# 07_Communication.net
KiCad netlist of a schematic drawn in Altium Designer
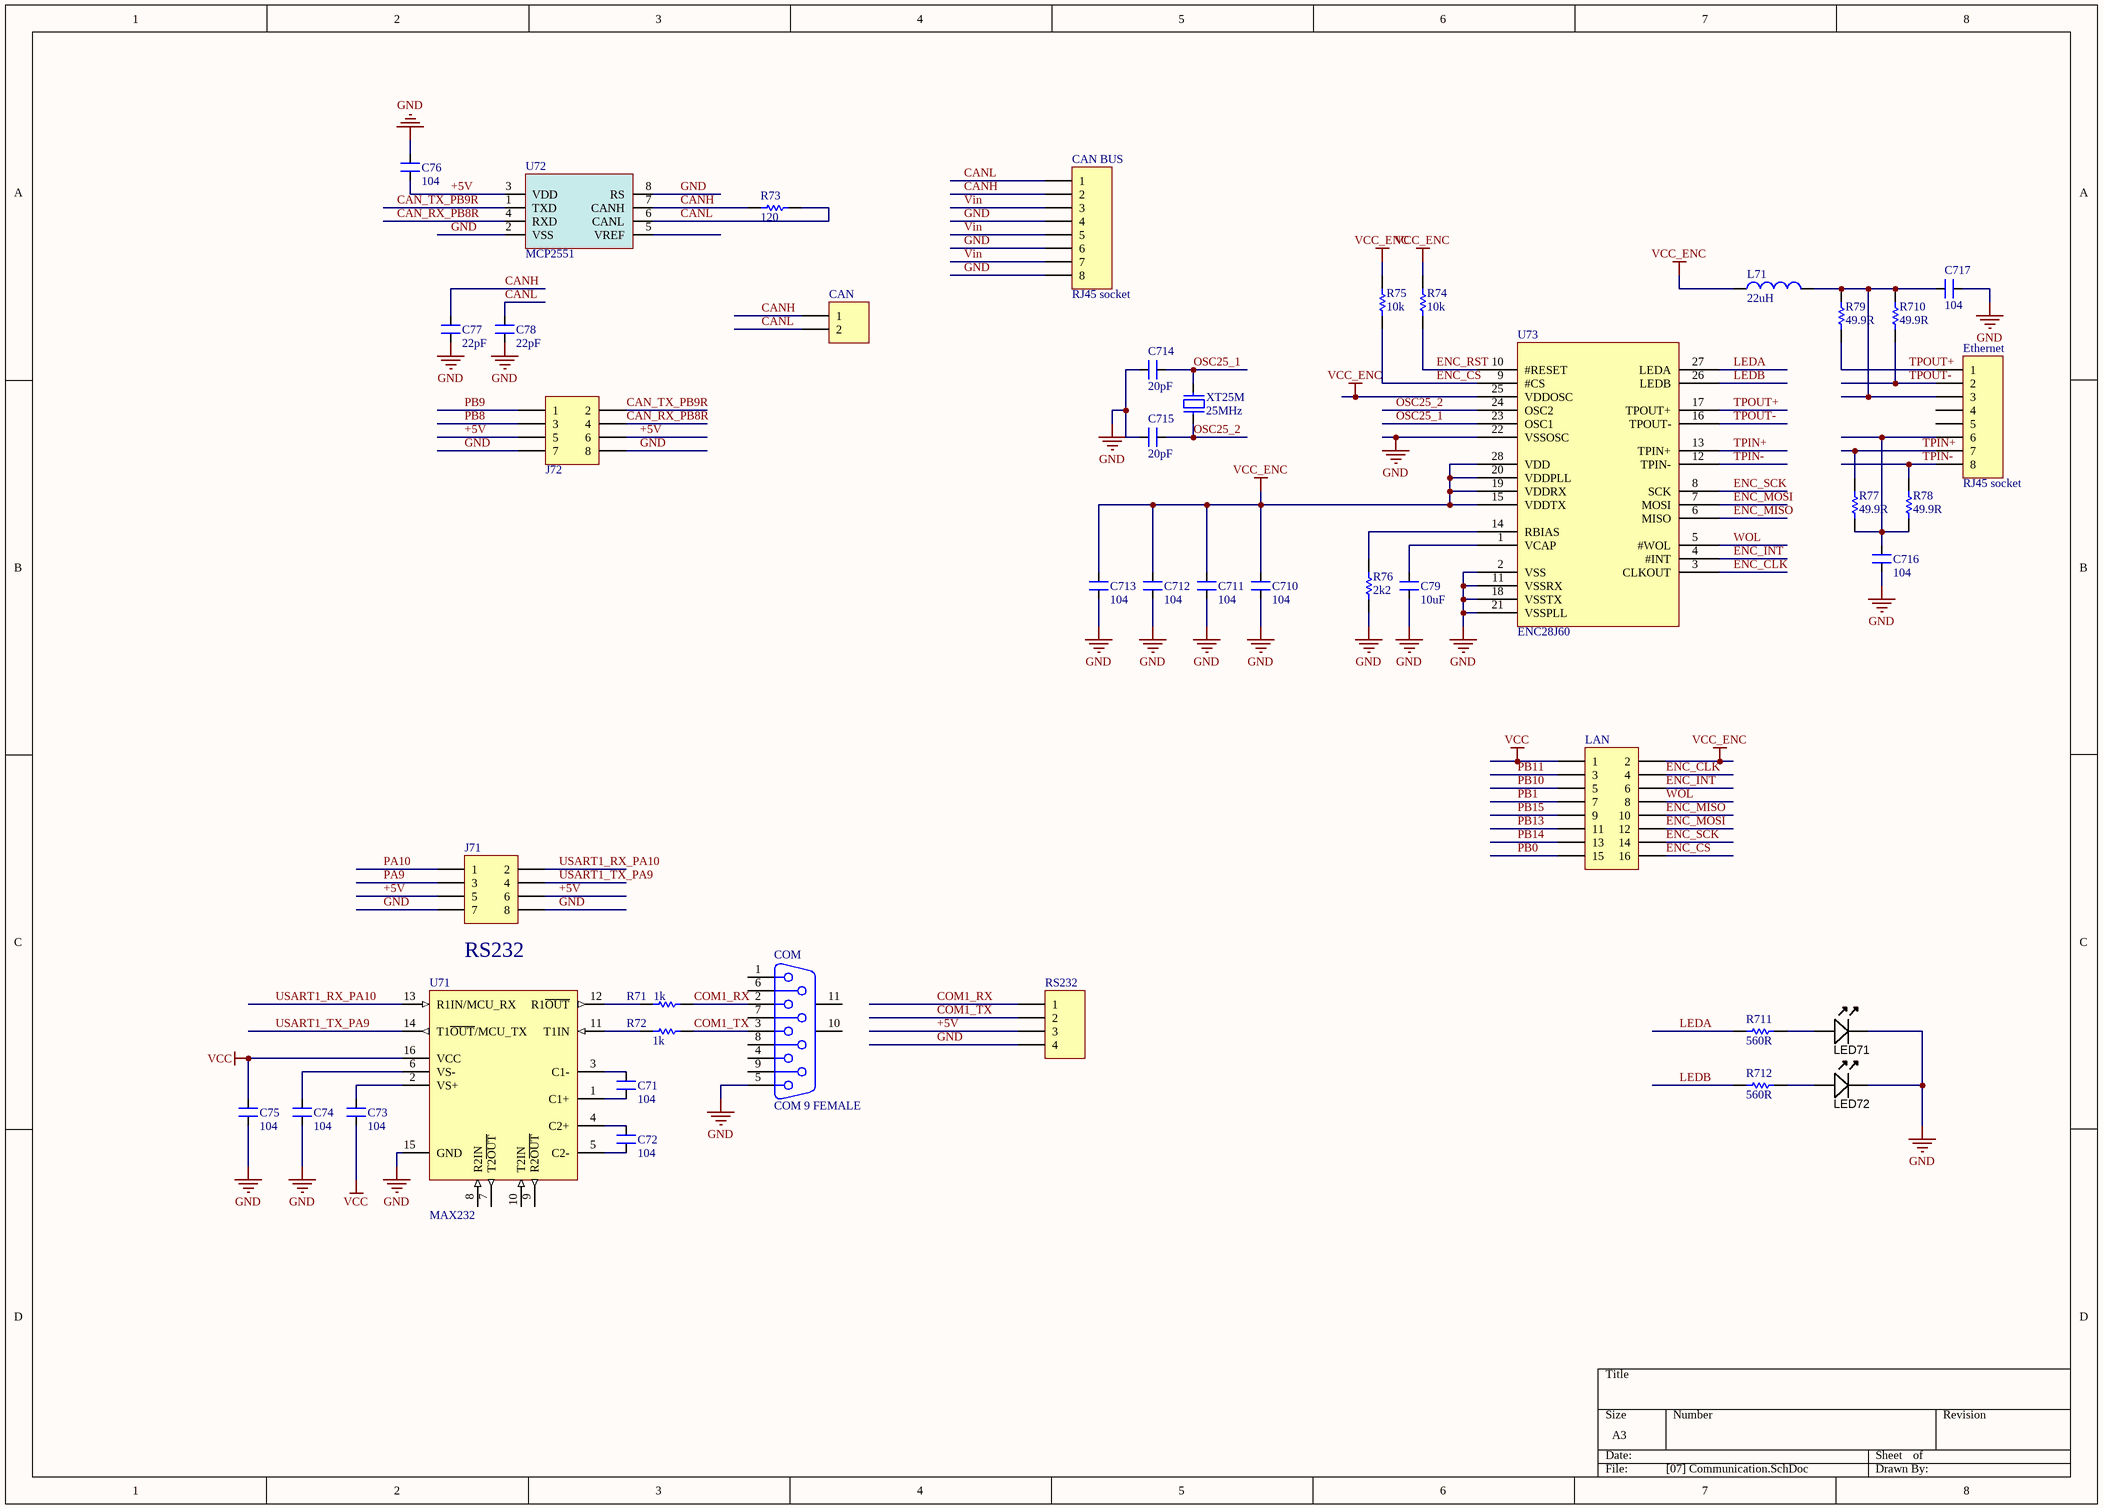
[diagram p0: [07] Communication.SchDoc]

(export (version "E")
  (design (tool "Eeschema 10.0.6"))
  (components
    (comp (ref "C71")
      (value "104")
      (footprint "CAPC2012N_F")
      (fields (field (name "Comment") "Cap_1206_104"))
      (libsource (lib "Tuan") (part "CAP NP"))
    )
    (comp (ref "C72")
      (value "104")
      (footprint "CAPC2012N_F")
      (fields (field (name "Comment") "Cap_1206_104"))
      (libsource (lib "Tuan") (part "CAP NP"))
    )
    (comp (ref "C73")
      (value "104")
      (footprint "CAPC2012N_F")
      (fields (field (name "Comment") "Cap_1206_104"))
      (libsource (lib "Tuan") (part "CAP NP"))
    )
    (comp (ref "C74")
      (value "104")
      (footprint "CAPC2012N_F")
      (fields (field (name "Comment") "Cap_1206_104"))
      (libsource (lib "Tuan") (part "CAP NP"))
    )
    (comp (ref "C75")
      (value "104")
      (footprint "CAPC2012N_F")
      (fields (field (name "Comment") "Cap_1206_104"))
      (libsource (lib "Tuan") (part "CAP NP"))
    )
    (comp (ref "C76")
      (value "104")
      (footprint "CAPC2012N_F")
      (fields (field (name "Comment") "Cap_10uF_0805"))
      (libsource (lib "Tuan") (part "CAP NP"))
    )
    (comp (ref "C77")
      (value "22pF")
      (footprint "CAPC1608N")
      (fields (field (name "Comment") "Cap_22p_0603"))
      (libsource (lib "Tuan") (part "CAP NP"))
    )
    (comp (ref "C78")
      (value "22pF")
      (footprint "CAPC1608N")
      (fields (field (name "Comment") "Cap_22p_0603"))
      (libsource (lib "Tuan") (part "CAP NP"))
    )
    (comp (ref "C79")
      (value "10uF")
      (footprint "CAPC2012N_F")
      (fields (field (name "Comment") "CAP NP"))
      (libsource (lib "Tuan") (part "CAP NP"))
    )
    (comp (ref "C710")
      (value "104")
      (footprint "CAPC1608N")
      (fields (field (name "Comment") "CAP NP"))
      (libsource (lib "Tuan") (part "CAP NP"))
    )
    (comp (ref "C711")
      (value "104")
      (footprint "CAPC1608N")
      (fields (field (name "Comment") "CAP NP"))
      (libsource (lib "Tuan") (part "CAP NP"))
    )
    (comp (ref "C712")
      (value "104")
      (footprint "CAPC1608N")
      (fields (field (name "Comment") "CAP NP"))
      (libsource (lib "Tuan") (part "CAP NP"))
    )
    (comp (ref "C713")
      (value "104")
      (footprint "CAPC1608N")
      (fields (field (name "Comment") "CAP NP"))
      (libsource (lib "Tuan") (part "CAP NP"))
    )
    (comp (ref "C714")
      (value "20pF")
      (footprint "CAPC1608N")
      (fields (field (name "Comment") "Cap_22p_0603"))
      (libsource (lib "Tuan") (part "CAP NP"))
    )
    (comp (ref "C715")
      (value "20pF")
      (footprint "CAPC1608N")
      (fields (field (name "Comment") "Cap_22p_0603"))
      (libsource (lib "Tuan") (part "CAP NP"))
    )
    (comp (ref "C716")
      (value "104")
      (footprint "CAPC2012N_F")
      (fields (field (name "Comment") "CAP NP"))
      (libsource (lib "Tuan") (part "CAP NP"))
    )
    (comp (ref "C717")
      (value "104")
      (footprint "CAPC2012N_F")
      (fields (field (name "Comment") "CAP NP"))
      (libsource (lib "Tuan") (part "CAP NP"))
    )
    (comp (ref "CAN")
      (value "Header 2")
      (footprint "HDR1X2")
      (description "Header, 2-Pin")
      (fields (field (name "PUBLISHER") "Altium Limited"))
      (libsource (lib "Miscellaneous Connectors") (part "Header 2"))
    )
    (comp (ref "CAN BUS")
      (value "RJ45 socket")
      (footprint "RJ45")
      (description "Header, 8-Pin")
      (fields (field (name "PUBLISHER") "Altium Limited"))
      (libsource (lib "Miscellaneous Connectors") (part "Header 8"))
    )
    (comp (ref "COM")
      (value "COM 9 FEMALE")
      (footprint "DB 9 Female")
      (fields (field (name "PUBLISHER") "Altium Limited"))
      (libsource (lib "heromap") (part "COM9M"))
    )
    (comp (ref "Ethernet")
      (value "RJ45 socket")
      (footprint "RJ45")
      (description "Header, 8-Pin")
      (fields (field (name "PUBLISHER") "Altium Limited"))
      (libsource (lib "Miscellaneous Connectors") (part "Header 8"))
    )
    (comp (ref "J71")
      (value "Header 4X2")
      (footprint "heromap:HDR2X4")
      (description "Header, 4-Pin, Dual row")
      (fields (field (name "PUBLISHER") "Altium Limited"))
      (libsource (lib "Miscellaneous Connectors") (part "Header 4X2"))
    )
    (comp (ref "J72")
      (value "Header 4X2")
      (footprint "heromap:HDR2X4")
      (description "Header, 4-Pin, Dual row")
      (fields (field (name "PUBLISHER") "Altium Limited"))
      (libsource (lib "heromap") (part "Header 4X2"))
    )
    (comp (ref "L71")
      (value "22uH")
      (footprint "CAPC2012N_F")
      (fields (field (name "Comment") "Inductor"))
      (libsource (lib "Tuan") (part "Inductor"))
    )
    (comp (ref "LAN")
      (value "Header 8X2")
      (footprint "heromap:HDR2X8")
      (description "Header, 8-Pin, Dual row")
      (fields (field (name "PUBLISHER") "Altium Limited"))
      (libsource (lib "heromap") (part "Header 8X2"))
    )
    (comp (ref "LED71")
      (value "Blue")
      (footprint "LED-0805-K")
      (description "LED 0805 SMD Blue 100mcd 470nm")
      (libsource (lib "PBL - Light Sources") (part "LED_SMD_Blue_0805_100mcd"))
    )
    (comp (ref "LED72")
      (value "Blue")
      (footprint "LED-0805-K")
      (description "LED 0805 SMD Blue 100mcd 470nm")
      (libsource (lib "PBL - Light Sources") (part "LED_SMD_Blue_0805_100mcd"))
    )
    (comp (ref "R71")
      (value "1k")
      (footprint "RESC2012N_F")
      (description "Tro dan 1k")
      (libsource (lib "Tuan") (part "Res"))
    )
    (comp (ref "R72")
      (value "1k")
      (footprint "RESC2012N_F")
      (description "Tro dan 1k")
      (libsource (lib "Tuan") (part "Res"))
    )
    (comp (ref "R73")
      (value "120")
      (footprint "RESC2012N_F")
      (fields (field (name "Comment") "Res_120_0805"))
      (libsource (lib "Tuan") (part "Res"))
    )
    (comp (ref "R74")
      (value "10k")
      (footprint "RESC1608N_ZERO")
      (fields (field (name "Comment") "Res"))
      (libsource (lib "Tuan") (part "Res"))
    )
    (comp (ref "R75")
      (value "10k")
      (footprint "RESC1608N_ZERO")
      (fields (field (name "Comment") "Res"))
      (libsource (lib "Tuan") (part "Res"))
    )
    (comp (ref "R76")
      (value "2k2")
      (footprint "RESC1608N_ZERO")
      (fields (field (name "Comment") "Res"))
      (libsource (lib "Tuan") (part "Res"))
    )
    (comp (ref "R77")
      (value "49.9R")
      (footprint "RESC2012N_F")
      (fields (field (name "Comment") "Res"))
      (libsource (lib "Tuan") (part "Res"))
    )
    (comp (ref "R78")
      (value "49.9R")
      (footprint "RESC2012N_F")
      (fields (field (name "Comment") "Res"))
      (libsource (lib "Tuan") (part "Res"))
    )
    (comp (ref "R79")
      (value "49.9R")
      (footprint "RESC2012N_F")
      (fields (field (name "Comment") "Res"))
      (libsource (lib "Tuan") (part "Res"))
    )
    (comp (ref "R710")
      (value "49.9R")
      (footprint "RESC2012N_F")
      (fields (field (name "Comment") "Res"))
      (libsource (lib "Tuan") (part "Res"))
    )
    (comp (ref "R711")
      (value "560R")
      (footprint "RESC1608N_ZERO")
      (fields (field (name "Comment") "Res"))
      (libsource (lib "Tuan") (part "Res"))
    )
    (comp (ref "R712")
      (value "560R")
      (footprint "RESC1608N_ZERO")
      (fields (field (name "Comment") "Res"))
      (libsource (lib "Tuan") (part "Res"))
    )
    (comp (ref "RS232")
      (value "Header 4")
      (footprint "HDR1X4")
      (description "Header, 4-Pin")
      (fields (field (name "PUBLISHER") "Altium Limited"))
      (libsource (lib "Miscellaneous Connectors") (part "Header 4"))
    )
    (comp (ref "U71")
      (value "MAX232")
      (footprint "SOIC127P600X175-16AN")
      (libsource (lib "Tuan") (part "MAX232"))
    )
    (comp (ref "U72") (value "MCP2551") (footprint "SOIC 8") (libsource (lib "Tuan") (part "MCP2551")))
    (comp (ref "U73") (value "ENC28J60") (footprint "SOIC-28") (libsource (lib "Tuan") (part "ENC28J60")))
    (comp (ref "XT25M") (value "25MHz") (footprint "XT2") (libsource (lib "Tuan") (part "Crystal")))
  )
  (nets
    (net (code "1") (name "/+5V") (class "Default")
      (node (ref "C76") (pin "2") (pinfunction "2_2") (pintype "passive"))
      (node (ref "J71") (pin "5") (pinfunction "5_5") (pintype "passive"))
      (node (ref "J71") (pin "6") (pinfunction "6_6") (pintype "passive"))
      (node (ref "J72") (pin "5") (pinfunction "5_5") (pintype "passive"))
      (node (ref "J72") (pin "6") (pinfunction "6_6") (pintype "passive"))
      (node (ref "RS232") (pin "3") (pinfunction "3_3") (pintype "passive"))
      (node (ref "U72") (pin "3") (pinfunction "VDD_3") (pintype "power_in"))
    )
    (net (code "2") (name "/CANH") (class "Default")
      (node (ref "C77") (pin "2") (pinfunction "2_2") (pintype "passive"))
      (node (ref "CAN") (pin "1") (pinfunction "1_1") (pintype "passive"))
      (node (ref "CAN BUS") (pin "2") (pinfunction "2_2") (pintype "passive"))
      (node (ref "R73") (pin "1") (pinfunction "1_1") (pintype "passive"))
      (node (ref "U72") (pin "7") (pinfunction "CANH_7") (pintype "power_in"))
    )
    (net (code "3") (name "/CANL") (class "Default")
      (node (ref "C78") (pin "2") (pinfunction "2_2") (pintype "passive"))
      (node (ref "CAN") (pin "2") (pinfunction "2_2") (pintype "passive"))
      (node (ref "CAN BUS") (pin "1") (pinfunction "1_1") (pintype "passive"))
      (node (ref "R73") (pin "2") (pinfunction "2_2") (pintype "passive"))
      (node (ref "U72") (pin "6") (pinfunction "CANL_6") (pintype "power_in"))
    )
    (net (code "4") (name "/CAN_RX_PB8R") (class "Default")
      (node (ref "J72") (pin "4") (pinfunction "4_4") (pintype "passive"))
      (node (ref "U72") (pin "4") (pinfunction "RXD_4") (pintype "power_in"))
    )
    (net (code "5") (name "/CAN_TX_PB9R") (class "Default")
      (node (ref "J72") (pin "2") (pinfunction "2_2") (pintype "passive"))
      (node (ref "U72") (pin "1") (pinfunction "TXD_1") (pintype "power_in"))
    )
    (net (code "6") (name "/COM1_RX") (class "Default")
      (node (ref "COM") (pin "2") (pinfunction "2_2") (pintype "passive"))
      (node (ref "R71") (pin "2") (pinfunction "2_2") (pintype "passive"))
      (node (ref "RS232") (pin "1") (pinfunction "1_1") (pintype "passive"))
    )
    (net (code "7") (name "/COM1_TX") (class "Default")
      (node (ref "COM") (pin "3") (pinfunction "3_3") (pintype "passive"))
      (node (ref "R72") (pin "2") (pinfunction "2_2") (pintype "passive"))
      (node (ref "RS232") (pin "2") (pinfunction "2_2") (pintype "passive"))
    )
    (net (code "8") (name "/ENC_CLK") (class "Default")
      (node (ref "LAN") (pin "4") (pinfunction "4_4") (pintype "passive"))
      (node (ref "U73") (pin "3") (pinfunction "CLKOUT_3") (pintype "passive"))
    )
    (net (code "9") (name "/ENC_CS") (class "Default")
      (node (ref "LAN") (pin "16") (pinfunction "16_16") (pintype "passive"))
      (node (ref "R75") (pin "1") (pinfunction "1_1") (pintype "passive"))
      (node (ref "U73") (pin "9") (pinfunction "#CS_9") (pintype "passive"))
    )
    (net (code "10") (name "/ENC_INT") (class "Default")
      (node (ref "LAN") (pin "6") (pinfunction "6_6") (pintype "passive"))
      (node (ref "U73") (pin "4") (pinfunction "#INT_4") (pintype "passive"))
    )
    (net (code "11") (name "/ENC_MISO") (class "Default")
      (node (ref "LAN") (pin "10") (pinfunction "10_10") (pintype "passive"))
      (node (ref "U73") (pin "6") (pinfunction "MISO_6") (pintype "passive"))
    )
    (net (code "12") (name "/ENC_MOSI") (class "Default")
      (node (ref "LAN") (pin "12") (pinfunction "12_12") (pintype "passive"))
      (node (ref "U73") (pin "7") (pinfunction "MOSI_7") (pintype "passive"))
    )
    (net (code "13") (name "/ENC_RST") (class "Default")
      (node (ref "R74") (pin "1") (pinfunction "1_1") (pintype "passive"))
      (node (ref "U73") (pin "10") (pinfunction "#RESET_10") (pintype "passive"))
    )
    (net (code "14") (name "/ENC_SCK") (class "Default")
      (node (ref "LAN") (pin "14") (pinfunction "14_14") (pintype "passive"))
      (node (ref "U73") (pin "8") (pinfunction "SCK_8") (pintype "passive"))
    )
    (net (code "15") (name "/LEDA") (class "Default")
      (node (ref "R711") (pin "1") (pinfunction "1_1") (pintype "passive"))
      (node (ref "U73") (pin "27") (pinfunction "LEDA_27") (pintype "passive"))
    )
    (net (code "16") (name "/LEDB") (class "Default")
      (node (ref "R712") (pin "1") (pinfunction "1_1") (pintype "passive"))
      (node (ref "U73") (pin "26") (pinfunction "LEDB_26") (pintype "passive"))
    )
    (net (code "17") (name "/OSC25_1") (class "Default")
      (node (ref "C714") (pin "1") (pinfunction "1_1") (pintype "passive"))
      (node (ref "U73") (pin "23") (pinfunction "OSC1_23") (pintype "passive"))
      (node (ref "XT25M") (pin "2") (pinfunction "2_2") (pintype "passive"))
    )
    (net (code "18") (name "/OSC25_2") (class "Default")
      (node (ref "C715") (pin "1") (pinfunction "1_1") (pintype "passive"))
      (node (ref "U73") (pin "24") (pinfunction "OSC2_24") (pintype "passive"))
      (node (ref "XT25M") (pin "1") (pinfunction "1_1") (pintype "passive"))
    )
    (net (code "19") (name "/PA9") (class "Default")
      (node (ref "J71") (pin "3") (pinfunction "3_3") (pintype "passive"))
    )
    (net (code "20") (name "/PA10") (class "Default")
      (node (ref "J71") (pin "1") (pinfunction "1_1") (pintype "passive"))
    )
    (net (code "21") (name "/PB0") (class "Default")
      (node (ref "LAN") (pin "15") (pinfunction "15_15") (pintype "passive"))
    )
    (net (code "22") (name "/PB1") (class "Default")
      (node (ref "LAN") (pin "7") (pinfunction "7_7") (pintype "passive"))
    )
    (net (code "23") (name "/PB8") (class "Default")
      (node (ref "J72") (pin "3") (pinfunction "3_3") (pintype "passive"))
    )
    (net (code "24") (name "/PB9") (class "Default")
      (node (ref "J72") (pin "1") (pinfunction "1_1") (pintype "passive"))
    )
    (net (code "25") (name "/PB10") (class "Default")
      (node (ref "LAN") (pin "5") (pinfunction "5_5") (pintype "passive"))
    )
    (net (code "26") (name "/PB11") (class "Default")
      (node (ref "LAN") (pin "3") (pinfunction "3_3") (pintype "passive"))
    )
    (net (code "27") (name "/PB13") (class "Default")
      (node (ref "LAN") (pin "11") (pinfunction "11_11") (pintype "passive"))
    )
    (net (code "28") (name "/PB14") (class "Default")
      (node (ref "LAN") (pin "13") (pinfunction "13_13") (pintype "passive"))
    )
    (net (code "29") (name "/PB15") (class "Default")
      (node (ref "LAN") (pin "9") (pinfunction "9_9") (pintype "passive"))
    )
    (net (code "30") (name "/TPIN+") (class "Default")
      (node (ref "Ethernet") (pin "7") (pinfunction "7_7") (pintype "passive"))
      (node (ref "R77") (pin "2") (pinfunction "2_2") (pintype "passive"))
      (node (ref "U73") (pin "13") (pinfunction "TPIN+_13") (pintype "passive"))
    )
    (net (code "31") (name "/TPIN-") (class "Default")
      (node (ref "Ethernet") (pin "8") (pinfunction "8_8") (pintype "passive"))
      (node (ref "R78") (pin "2") (pinfunction "2_2") (pintype "passive"))
      (node (ref "U73") (pin "12") (pinfunction "TPIN-_12") (pintype "passive"))
    )
    (net (code "32") (name "/TPOUT+") (class "Default")
      (node (ref "Ethernet") (pin "1") (pinfunction "1_1") (pintype "passive"))
      (node (ref "R79") (pin "1") (pinfunction "1_1") (pintype "passive"))
      (node (ref "U73") (pin "17") (pinfunction "TPOUT+_17") (pintype "passive"))
    )
    (net (code "33") (name "/TPOUT-") (class "Default")
      (node (ref "Ethernet") (pin "2") (pinfunction "2_2") (pintype "passive"))
      (node (ref "R710") (pin "1") (pinfunction "1_1") (pintype "passive"))
      (node (ref "U73") (pin "16") (pinfunction "TPOUT-_16") (pintype "passive"))
    )
    (net (code "34") (name "/USART1_RX_PA10") (class "Default")
      (node (ref "J71") (pin "2") (pinfunction "2_2") (pintype "passive"))
      (node (ref "U71") (pin "13") (pinfunction "R1IN/MCU_RX_13") (pintype "input"))
    )
    (net (code "35") (name "/USART1_TX_PA9") (class "Default")
      (node (ref "J71") (pin "4") (pinfunction "4_4") (pintype "passive"))
      (node (ref "U71") (pin "14") (pinfunction "T1~{OUT}/MCU_TX_14") (pintype "output"))
    )
    (net (code "36") (name "/Vin") (class "Default")
      (node (ref "CAN BUS") (pin "3") (pinfunction "3_3") (pintype "passive"))
      (node (ref "CAN BUS") (pin "5") (pinfunction "5_5") (pintype "passive"))
      (node (ref "CAN BUS") (pin "7") (pinfunction "7_7") (pintype "passive"))
    )
    (net (code "37") (name "/WOL") (class "Default")
      (node (ref "LAN") (pin "8") (pinfunction "8_8") (pintype "passive"))
      (node (ref "U73") (pin "5") (pinfunction "#WOL_5") (pintype "passive"))
    )
    (net (code "38") (name "GND") (class "Default")
      (node (ref "C710") (pin "1") (pinfunction "1_1") (pintype "passive"))
      (node (ref "C711") (pin "1") (pinfunction "1_1") (pintype "passive"))
      (node (ref "C712") (pin "1") (pinfunction "1_1") (pintype "passive"))
      (node (ref "C713") (pin "1") (pinfunction "1_1") (pintype "passive"))
      (node (ref "C714") (pin "2") (pinfunction "2_2") (pintype "passive"))
      (node (ref "C715") (pin "2") (pinfunction "2_2") (pintype "passive"))
      (node (ref "C716") (pin "1") (pinfunction "1_1") (pintype "passive"))
      (node (ref "C717") (pin "2") (pinfunction "2_2") (pintype "passive"))
      (node (ref "C74") (pin "1") (pinfunction "1_1") (pintype "passive"))
      (node (ref "C75") (pin "1") (pinfunction "1_1") (pintype "passive"))
      (node (ref "C76") (pin "1") (pinfunction "1_1") (pintype "passive"))
      (node (ref "C77") (pin "1") (pinfunction "1_1") (pintype "passive"))
      (node (ref "C78") (pin "1") (pinfunction "1_1") (pintype "passive"))
      (node (ref "C79") (pin "1") (pinfunction "1_1") (pintype "passive"))
      (node (ref "CAN BUS") (pin "4") (pinfunction "4_4") (pintype "passive"))
      (node (ref "CAN BUS") (pin "6") (pinfunction "6_6") (pintype "passive"))
      (node (ref "CAN BUS") (pin "8") (pinfunction "8_8") (pintype "passive"))
      (node (ref "COM") (pin "5") (pinfunction "5_5") (pintype "passive"))
      (node (ref "J71") (pin "7") (pinfunction "7_7") (pintype "passive"))
      (node (ref "J71") (pin "8") (pinfunction "8_8") (pintype "passive"))
      (node (ref "J72") (pin "7") (pinfunction "7_7") (pintype "passive"))
      (node (ref "J72") (pin "8") (pinfunction "8_8") (pintype "passive"))
      (node (ref "LED71") (pin "K") (pinfunction "K_K") (pintype "passive"))
      (node (ref "LED72") (pin "K") (pinfunction "K_K") (pintype "passive"))
      (node (ref "R76") (pin "1") (pinfunction "1_1") (pintype "passive"))
      (node (ref "RS232") (pin "4") (pinfunction "4_4") (pintype "passive"))
      (node (ref "U71") (pin "15") (pinfunction "GND_15") (pintype "power_in"))
      (node (ref "U72") (pin "2") (pinfunction "VSS_2") (pintype "power_in"))
      (node (ref "U72") (pin "8") (pinfunction "RS_8") (pintype "power_in"))
      (node (ref "U73") (pin "11") (pinfunction "VSSRX_11") (pintype "passive"))
      (node (ref "U73") (pin "18") (pinfunction "VSSTX_18") (pintype "passive"))
      (node (ref "U73") (pin "2") (pinfunction "VSS_2") (pintype "passive"))
      (node (ref "U73") (pin "21") (pinfunction "VSSPLL_21") (pintype "passive"))
      (node (ref "U73") (pin "22") (pinfunction "VSSOSC_22") (pintype "passive"))
    )
    (net (code "39") (name "Net-(C716-Pad2)") (class "Default")
      (node (ref "C716") (pin "2") (pinfunction "2_2") (pintype "passive"))
      (node (ref "Ethernet") (pin "6") (pinfunction "6_6") (pintype "passive"))
      (node (ref "R77") (pin "1") (pinfunction "1_1") (pintype "passive"))
      (node (ref "R78") (pin "1") (pinfunction "1_1") (pintype "passive"))
    )
    (net (code "40") (name "Net-(C717-Pad1)") (class "Default")
      (node (ref "C717") (pin "1") (pinfunction "1_1") (pintype "passive"))
      (node (ref "Ethernet") (pin "3") (pinfunction "3_3") (pintype "passive"))
      (node (ref "L71") (pin "2") (pinfunction "2_2") (pintype "passive"))
      (node (ref "R710") (pin "2") (pinfunction "2_2") (pintype "passive"))
      (node (ref "R79") (pin "2") (pinfunction "2_2") (pintype "passive"))
    )
    (net (code "41") (name "Net-(LED71-PadA)") (class "Default")
      (node (ref "LED71") (pin "A") (pinfunction "A_A") (pintype "passive"))
      (node (ref "R711") (pin "2") (pinfunction "2_2") (pintype "passive"))
    )
    (net (code "42") (name "Net-(LED72-PadA)") (class "Default")
      (node (ref "LED72") (pin "A") (pinfunction "A_A") (pintype "passive"))
      (node (ref "R712") (pin "2") (pinfunction "2_2") (pintype "passive"))
    )
    (net (code "43") (name "Net-(U71-C1+)") (class "Default")
      (node (ref "C71") (pin "1") (pinfunction "1_1") (pintype "passive"))
      (node (ref "U71") (pin "1") (pinfunction "C1+_1") (pintype "passive"))
    )
    (net (code "44") (name "Net-(U71-C1-)") (class "Default")
      (node (ref "C71") (pin "2") (pinfunction "2_2") (pintype "passive"))
      (node (ref "U71") (pin "3") (pinfunction "C1-_3") (pintype "passive"))
    )
    (net (code "45") (name "Net-(U71-C2+)") (class "Default")
      (node (ref "C72") (pin "2") (pinfunction "2_2") (pintype "passive"))
      (node (ref "U71") (pin "4") (pinfunction "C2+_4") (pintype "passive"))
    )
    (net (code "46") (name "Net-(U71-C2-)") (class "Default")
      (node (ref "C72") (pin "1") (pinfunction "1_1") (pintype "passive"))
      (node (ref "U71") (pin "5") (pinfunction "C2-_5") (pintype "passive"))
    )
    (net (code "47") (name "Net-(U71-R1~{OUT})") (class "Default")
      (node (ref "R71") (pin "1") (pinfunction "1_1") (pintype "passive"))
      (node (ref "U71") (pin "12") (pinfunction "R1~{OUT}_12") (pintype "output"))
    )
    (net (code "48") (name "Net-(U71-T1IN)") (class "Default")
      (node (ref "R72") (pin "1") (pinfunction "1_1") (pintype "passive"))
      (node (ref "U71") (pin "11") (pinfunction "T1IN_11") (pintype "input"))
    )
    (net (code "49") (name "Net-(U71-VS+)") (class "Default")
      (node (ref "C73") (pin "2") (pinfunction "2_2") (pintype "passive"))
      (node (ref "U71") (pin "2") (pinfunction "VS+_2") (pintype "power_in"))
    )
    (net (code "50") (name "Net-(U71-VS-)") (class "Default")
      (node (ref "C74") (pin "2") (pinfunction "2_2") (pintype "passive"))
      (node (ref "U71") (pin "6") (pinfunction "VS-_6") (pintype "power_in"))
    )
    (net (code "51") (name "Net-(U73-RBIAS)") (class "Default")
      (node (ref "R76") (pin "2") (pinfunction "2_2") (pintype "passive"))
      (node (ref "U73") (pin "14") (pinfunction "RBIAS_14") (pintype "passive"))
    )
    (net (code "52") (name "Net-(U73-VCAP)") (class "Default")
      (node (ref "C79") (pin "2") (pinfunction "2_2") (pintype "passive"))
      (node (ref "U73") (pin "1") (pinfunction "VCAP_1") (pintype "passive"))
    )
    (net (code "53") (name "VCC") (class "Default")
      (node (ref "C73") (pin "1") (pinfunction "1_1") (pintype "passive"))
      (node (ref "C75") (pin "2") (pinfunction "2_2") (pintype "passive"))
      (node (ref "LAN") (pin "1") (pinfunction "1_1") (pintype "passive"))
      (node (ref "U71") (pin "16") (pinfunction "VCC_16") (pintype "power_in"))
    )
    (net (code "54") (name "VCC_ENC") (class "Default")
      (node (ref "C710") (pin "2") (pinfunction "2_2") (pintype "passive"))
      (node (ref "C711") (pin "2") (pinfunction "2_2") (pintype "passive"))
      (node (ref "C712") (pin "2") (pinfunction "2_2") (pintype "passive"))
      (node (ref "C713") (pin "2") (pinfunction "2_2") (pintype "passive"))
      (node (ref "L71") (pin "1") (pinfunction "1_1") (pintype "passive"))
      (node (ref "LAN") (pin "2") (pinfunction "2_2") (pintype "passive"))
      (node (ref "R74") (pin "2") (pinfunction "2_2") (pintype "passive"))
      (node (ref "R75") (pin "2") (pinfunction "2_2") (pintype "passive"))
      (node (ref "U73") (pin "15") (pinfunction "VDDTX_15") (pintype "passive"))
      (node (ref "U73") (pin "19") (pinfunction "VDDRX_19") (pintype "passive"))
      (node (ref "U73") (pin "20") (pinfunction "VDDPLL_20") (pintype "passive"))
      (node (ref "U73") (pin "25") (pinfunction "VDDOSC_25") (pintype "passive"))
      (node (ref "U73") (pin "28") (pinfunction "VDD_28") (pintype "passive"))
    )
    (net (code "55") (name "unconnected-(COM-MH1-Pad10)") (class "Default")
      (node (ref "COM") (pin "10") (pinfunction "MH1_10") (pintype "passive"))
    )
    (net (code "56") (name "unconnected-(COM-MH2-Pad11)") (class "Default")
      (node (ref "COM") (pin "11") (pinfunction "MH2_11") (pintype "passive"))
    )
    (net (code "57") (name "unconnected-(COM-Pad1)") (class "Default")
      (node (ref "COM") (pin "1") (pinfunction "1_1") (pintype "passive"))
    )
    (net (code "58") (name "unconnected-(COM-Pad4)") (class "Default")
      (node (ref "COM") (pin "4") (pinfunction "4_4") (pintype "passive"))
    )
    (net (code "59") (name "unconnected-(COM-Pad6)") (class "Default")
      (node (ref "COM") (pin "6") (pinfunction "6_6") (pintype "passive"))
    )
    (net (code "60") (name "unconnected-(COM-Pad7)") (class "Default")
      (node (ref "COM") (pin "7") (pinfunction "7_7") (pintype "passive"))
    )
    (net (code "61") (name "unconnected-(COM-Pad8)") (class "Default")
      (node (ref "COM") (pin "8") (pinfunction "8_8") (pintype "passive"))
    )
    (net (code "62") (name "unconnected-(COM-Pad9)") (class "Default")
      (node (ref "COM") (pin "9") (pinfunction "9_9") (pintype "passive"))
    )
    (net (code "63") (name "unconnected-(Ethernet-Pad4)") (class "Default")
      (node (ref "Ethernet") (pin "4") (pinfunction "4_4") (pintype "passive"))
    )
    (net (code "64") (name "unconnected-(Ethernet-Pad5)") (class "Default")
      (node (ref "Ethernet") (pin "5") (pinfunction "5_5") (pintype "passive"))
    )
    (net (code "65") (name "unconnected-(U71-R2IN-Pad8)") (class "Default")
      (node (ref "U71") (pin "8") (pinfunction "R2IN_8") (pintype "input"))
    )
    (net (code "66") (name "unconnected-(U71-R2~{OUT}-Pad9)") (class "Default")
      (node (ref "U71") (pin "9") (pinfunction "R2~{OUT}_9") (pintype "output"))
    )
    (net (code "67") (name "unconnected-(U71-T2IN-Pad10)") (class "Default")
      (node (ref "U71") (pin "10") (pinfunction "T2IN_10") (pintype "input"))
    )
    (net (code "68") (name "unconnected-(U71-T2~{OUT}-Pad7)") (class "Default")
      (node (ref "U71") (pin "7") (pinfunction "T2~{OUT}_7") (pintype "output"))
    )
    (net (code "69") (name "unconnected-(U72-VREF-Pad5)") (class "Default")
      (node (ref "U72") (pin "5") (pinfunction "VREF_5") (pintype "power_in"))
    )
  )
)
